# Sheet1.net
KiCad netlist of a schematic drawn in Altium Designer
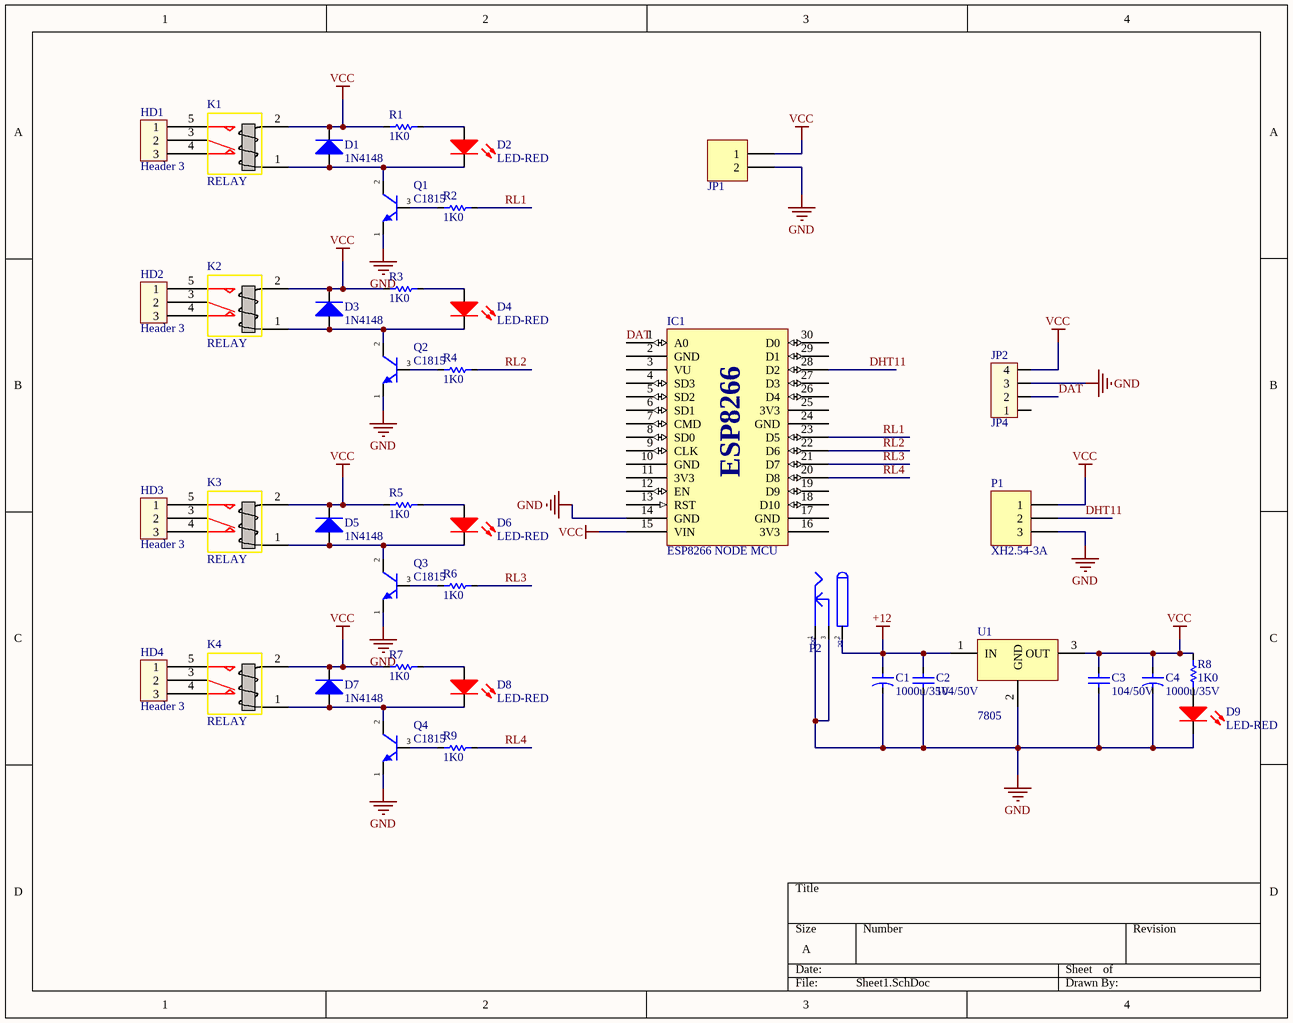
[diagram p0: Sheet1.SchDoc]

(export (version "E")
  (design (tool "Eeschema 10.0.6"))
  (components
    (comp (ref "C1")
      (value "1000u/35V")
      (footprint "CAP 13x25x5")
      (description "1000uF 35V Through Hole Aluminum Electrolytic Capacitor")
      (libsource (lib "Capacitors-Smile-Lib") (part "1000u/35V (13x25x5)"))
    )
    (comp (ref "C2")
      (value "104/50V")
      (footprint "CAP_NP_100")
      (libsource (lib "Capacitors-Smile-Lib") (part "CER-104-50V"))
    )
    (comp (ref "C3")
      (value "104/50V")
      (footprint "CAP_NP_100")
      (libsource (lib "Capacitors-Smile-Lib") (part "CER-104-50V"))
    )
    (comp (ref "C4")
      (value "1000u/35V")
      (footprint "CAP 13x25x5")
      (description "1000uF 35V Through Hole Aluminum Electrolytic Capacitor")
      (libsource (lib "Capacitors-Smile-Lib") (part "1000u/35V (13x25x5)"))
    )
    (comp (ref "D1")
      (value "1N4148")
      (footprint "DO35-GLASS-300MIL")
      (description "0.2A 75V Diode Standard Through Hole DO-35")
      (libsource (lib "Diodes-Smile-Lib") (part "1N4148 DO35"))
    )
    (comp (ref "D2")
      (value "LED-RED")
      (footprint "LED-3mm")
      (libsource (lib "LED-Smile-Lib") (part "LED-3MM-RED-LENS_RED"))
    )
    (comp (ref "D3")
      (value "1N4148")
      (footprint "DO35-GLASS-300MIL")
      (description "0.2A 75V Diode Standard Through Hole DO-35")
      (libsource (lib "Diodes-Smile-Lib") (part "1N4148 DO35"))
    )
    (comp (ref "D4")
      (value "LED-RED")
      (footprint "LED-3mm")
      (libsource (lib "LED-Smile-Lib") (part "LED-3MM-RED-LENS_RED"))
    )
    (comp (ref "D5")
      (value "1N4148")
      (footprint "DO35-GLASS-300MIL")
      (description "0.2A 75V Diode Standard Through Hole DO-35")
      (libsource (lib "Diodes-Smile-Lib") (part "1N4148 DO35"))
    )
    (comp (ref "D6")
      (value "LED-RED")
      (footprint "LED-3mm")
      (libsource (lib "LED-Smile-Lib") (part "LED-3MM-RED-LENS_RED"))
    )
    (comp (ref "D7")
      (value "1N4148")
      (footprint "DO35-GLASS-300MIL")
      (description "0.2A 75V Diode Standard Through Hole DO-35")
      (libsource (lib "Diodes-Smile-Lib") (part "1N4148 DO35"))
    )
    (comp (ref "D8")
      (value "LED-RED")
      (footprint "LED-3mm")
      (libsource (lib "LED-Smile-Lib") (part "LED-3MM-RED-LENS_RED"))
    )
    (comp (ref "D9")
      (value "LED-RED")
      (footprint "LED-3mm")
      (libsource (lib "LED-Smile-Lib") (part "LED-3MM-RED-LENS_RED"))
    )
    (comp (ref "HD1")
      (value "Header 3")
      (footprint "HED3")
      (description "Header 3 (Green)")
      (libsource (lib "syhaunguyen") (part "Hed3"))
    )
    (comp (ref "HD2")
      (value "Header 3")
      (footprint "HED3")
      (description "Header 3 (Green)")
      (libsource (lib "syhaunguyen") (part "Hed3"))
    )
    (comp (ref "HD3")
      (value "Header 3")
      (footprint "HED3")
      (description "Header 3 (Green)")
      (libsource (lib "syhaunguyen") (part "Hed3"))
    )
    (comp (ref "HD4")
      (value "Header 3")
      (footprint "HED3")
      (description "Header 3 (Green)")
      (libsource (lib "syhaunguyen") (part "Hed3"))
    )
    (comp (ref "IC1")
      (value "ESP8266 NODE MCU")
      (footprint "ESP8266 NodeMCU")
      (description "LUA-ESP8266 Wifi Module Techmt.vn")
      (libsource (lib "thuviencuatu") (part "ESP8266 NodeMCU"))
    )
    (comp (ref "JP1")
      (value "Header 2_1")
      (footprint "HED2")
      (description "Header, 2-Pin")
      (fields (field (name "MANUFACTURER") "Generic Components"))
      (libsource (lib "syhaunguyen") (part "Header 2_1"))
    )
    (comp (ref "JP2")
      (value "JP4")
      (footprint "CON4")
      (description "Connector 4")
      (libsource (lib "syhaunguyen") (part "Con4"))
    )
    (comp (ref "K1")
      (value "RELAY")
      (footprint "RELAY 12V_112D1")
      (libsource (lib "Relay-Smile-Lib") (part "RELAY 4"))
    )
    (comp (ref "K2")
      (value "RELAY")
      (footprint "RELAY 12V_112D1")
      (libsource (lib "Relay-Smile-Lib") (part "RELAY 4"))
    )
    (comp (ref "K3")
      (value "RELAY")
      (footprint "RELAY 12V_112D1")
      (libsource (lib "Relay-Smile-Lib") (part "RELAY 4"))
    )
    (comp (ref "K4")
      (value "RELAY")
      (footprint "RELAY 12V_112D1")
      (libsource (lib "Relay-Smile-Lib") (part "RELAY 4"))
    )
    (comp (ref "P1")
      (value "XH2.54-3A")
      (footprint "XH2.54-3A")
      (libsource (lib "XH2.54-Smile-Lib") (part "XH2.54-3A"))
    )
    (comp (ref "P2")
      (value "DC005")
      (footprint "JACK DC 5.5x2")
      (description "Jack DC 5.5x2.1")
      (libsource (lib "Power Jack-Smile-Lib") (part "JACK DC5.5x2.1"))
    )
    (comp (ref "Q1")
      (value "C1815")
      (footprint "TO-92")
      (description "TRANS NPN 50V 0.15A TO-92")
      (libsource (lib "BJT-Smile-Lib") (part "C1815-TO92"))
    )
    (comp (ref "Q2")
      (value "C1815")
      (footprint "TO-92")
      (description "TRANS NPN 50V 0.15A TO-92")
      (libsource (lib "BJT-Smile-Lib") (part "C1815-TO92"))
    )
    (comp (ref "Q3")
      (value "C1815")
      (footprint "TO-92")
      (description "TRANS NPN 50V 0.15A TO-92")
      (libsource (lib "BJT-Smile-Lib") (part "C1815-TO92"))
    )
    (comp (ref "Q4")
      (value "C1815")
      (footprint "TO-92")
      (description "TRANS NPN 50V 0.15A TO-92")
      (libsource (lib "BJT-Smile-Lib") (part "C1815-TO92"))
    )
    (comp (ref "R1")
      (value "1K0")
      (footprint "R-300mil")
      (description "RES 1K OHM 1/4W 5% CARBON FILM")
      (libsource (lib "RES-0.25W-Smile-Lib") (part "R-1/4W-5%-1K0"))
    )
    (comp (ref "R2")
      (value "1K0")
      (footprint "R-300mil")
      (description "RES 1K OHM 1/4W 5% CARBON FILM")
      (libsource (lib "RES-0.25W-Smile-Lib") (part "R-1/4W-5%-1K0"))
    )
    (comp (ref "R3")
      (value "1K0")
      (footprint "R-300mil")
      (description "RES 1K OHM 1/4W 5% CARBON FILM")
      (libsource (lib "RES-0.25W-Smile-Lib") (part "R-1/4W-5%-1K0"))
    )
    (comp (ref "R4")
      (value "1K0")
      (footprint "R-300mil")
      (description "RES 1K OHM 1/4W 5% CARBON FILM")
      (libsource (lib "RES-0.25W-Smile-Lib") (part "R-1/4W-5%-1K0"))
    )
    (comp (ref "R5")
      (value "1K0")
      (footprint "R-300mil")
      (description "RES 1K OHM 1/4W 5% CARBON FILM")
      (libsource (lib "RES-0.25W-Smile-Lib") (part "R-1/4W-5%-1K0"))
    )
    (comp (ref "R6")
      (value "1K0")
      (footprint "R-300mil")
      (description "RES 1K OHM 1/4W 5% CARBON FILM")
      (libsource (lib "RES-0.25W-Smile-Lib") (part "R-1/4W-5%-1K0"))
    )
    (comp (ref "R7")
      (value "1K0")
      (footprint "R-300mil")
      (description "RES 1K OHM 1/4W 5% CARBON FILM")
      (libsource (lib "RES-0.25W-Smile-Lib") (part "R-1/4W-5%-1K0"))
    )
    (comp (ref "R8")
      (value "1K0")
      (footprint "R-300mil")
      (description "RES 1K OHM 1/4W 5% CARBON FILM")
      (libsource (lib "RES-0.25W-Smile-Lib") (part "R-1/4W-5%-1K0"))
    )
    (comp (ref "R9")
      (value "1K0")
      (footprint "R-300mil")
      (description "RES 1K OHM 1/4W 5% CARBON FILM")
      (libsource (lib "RES-0.25W-Smile-Lib") (part "R-1/4W-5%-1K0"))
    )
    (comp (ref "U1")
      (value "7805")
      (footprint "TO 220+TN")
      (description "Linear Voltage Regulator IC Positive Fixed 1 Output 5V 1A TO-220AB")
      (libsource (lib "Linear Regulator-Smile-Lib") (part "7805 TO-220"))
    )
  )
  (nets
    (net (code "1") (name "+12") (class "Default")
      (node (ref "C1") (pin "1") (pinfunction "1_1") (pintype "passive"))
      (node (ref "C2") (pin "1") (pinfunction "1_1") (pintype "passive"))
      (node (ref "P2") (pin "2") (pinfunction "2_2") (pintype "power_in"))
      (node (ref "U1") (pin "1") (pinfunction "IN_1") (pintype "power_in"))
    )
    (net (code "2") (name "/DAT") (class "Default")
      (node (ref "IC1") (pin "1") (pinfunction "A0_1") (pintype "bidirectional"))
      (node (ref "JP2") (pin "2") (pinfunction "2_2") (pintype "passive"))
    )
    (net (code "3") (name "/DHT11") (class "Default")
      (node (ref "IC1") (pin "28") (pinfunction "D2_28") (pintype "bidirectional"))
      (node (ref "P1") (pin "2") (pinfunction "2_2") (pintype "passive"))
    )
    (net (code "4") (name "/RL1") (class "Default")
      (node (ref "IC1") (pin "23") (pinfunction "D5_23") (pintype "bidirectional"))
      (node (ref "R2") (pin "1") (pinfunction "1_1") (pintype "passive"))
    )
    (net (code "5") (name "/RL2") (class "Default")
      (node (ref "IC1") (pin "22") (pinfunction "D6_22") (pintype "bidirectional"))
      (node (ref "R4") (pin "1") (pinfunction "1_1") (pintype "passive"))
    )
    (net (code "6") (name "/RL3") (class "Default")
      (node (ref "IC1") (pin "21") (pinfunction "D7_21") (pintype "bidirectional"))
      (node (ref "R6") (pin "1") (pinfunction "1_1") (pintype "passive"))
    )
    (net (code "7") (name "/RL4") (class "Default")
      (node (ref "IC1") (pin "20") (pinfunction "D8_20") (pintype "bidirectional"))
      (node (ref "R9") (pin "1") (pinfunction "1_1") (pintype "passive"))
    )
    (net (code "8") (name "GND") (class "Default")
      (node (ref "C1") (pin "2") (pinfunction "2_2") (pintype "passive"))
      (node (ref "C2") (pin "2") (pinfunction "2_2") (pintype "passive"))
      (node (ref "C3") (pin "2") (pinfunction "2_2") (pintype "passive"))
      (node (ref "C4") (pin "2") (pinfunction "2_2") (pintype "passive"))
      (node (ref "D9") (pin "2") (pinfunction "K_2") (pintype "passive"))
      (node (ref "IC1") (pin "14") (pinfunction "GND_14") (pintype "power_in"))
      (node (ref "JP1") (pin "2") (pinfunction "2_2") (pintype "passive"))
      (node (ref "JP2") (pin "3") (pinfunction "3_3") (pintype "passive"))
      (node (ref "P1") (pin "3") (pinfunction "3_3") (pintype "passive"))
      (node (ref "P2") (pin "1") (pinfunction "1_1") (pintype "power_in"))
      (node (ref "P2") (pin "3") (pinfunction "3_3") (pintype "power_in"))
      (node (ref "Q1") (pin "1") (pinfunction "E_1") (pintype "passive"))
      (node (ref "Q2") (pin "1") (pinfunction "E_1") (pintype "passive"))
      (node (ref "Q3") (pin "1") (pinfunction "E_1") (pintype "passive"))
      (node (ref "Q4") (pin "1") (pinfunction "E_1") (pintype "passive"))
      (node (ref "U1") (pin "2") (pinfunction "GND_2") (pintype "power_in"))
    )
    (net (code "9") (name "Net-(D1-A)") (class "Default")
      (node (ref "D1") (pin "1") (pinfunction "A_1") (pintype "passive"))
      (node (ref "D2") (pin "2") (pinfunction "K_2") (pintype "passive"))
      (node (ref "K1") (pin "1") (pinfunction "Coil1_1") (pintype "passive"))
      (node (ref "Q1") (pin "2") (pinfunction "C_2") (pintype "passive"))
    )
    (net (code "10") (name "Net-(D2-A)") (class "Default")
      (node (ref "D2") (pin "1") (pinfunction "A_1") (pintype "passive"))
      (node (ref "R1") (pin "1") (pinfunction "1_1") (pintype "passive"))
    )
    (net (code "11") (name "Net-(D3-A)") (class "Default")
      (node (ref "D3") (pin "1") (pinfunction "A_1") (pintype "passive"))
      (node (ref "D4") (pin "2") (pinfunction "K_2") (pintype "passive"))
      (node (ref "K2") (pin "1") (pinfunction "Coil1_1") (pintype "passive"))
      (node (ref "Q2") (pin "2") (pinfunction "C_2") (pintype "passive"))
    )
    (net (code "12") (name "Net-(D4-A)") (class "Default")
      (node (ref "D4") (pin "1") (pinfunction "A_1") (pintype "passive"))
      (node (ref "R3") (pin "1") (pinfunction "1_1") (pintype "passive"))
    )
    (net (code "13") (name "Net-(D5-A)") (class "Default")
      (node (ref "D5") (pin "1") (pinfunction "A_1") (pintype "passive"))
      (node (ref "D6") (pin "2") (pinfunction "K_2") (pintype "passive"))
      (node (ref "K3") (pin "1") (pinfunction "Coil1_1") (pintype "passive"))
      (node (ref "Q3") (pin "2") (pinfunction "C_2") (pintype "passive"))
    )
    (net (code "14") (name "Net-(D6-A)") (class "Default")
      (node (ref "D6") (pin "1") (pinfunction "A_1") (pintype "passive"))
      (node (ref "R5") (pin "1") (pinfunction "1_1") (pintype "passive"))
    )
    (net (code "15") (name "Net-(D7-A)") (class "Default")
      (node (ref "D7") (pin "1") (pinfunction "A_1") (pintype "passive"))
      (node (ref "D8") (pin "2") (pinfunction "K_2") (pintype "passive"))
      (node (ref "K4") (pin "1") (pinfunction "Coil1_1") (pintype "passive"))
      (node (ref "Q4") (pin "2") (pinfunction "C_2") (pintype "passive"))
    )
    (net (code "16") (name "Net-(D8-A)") (class "Default")
      (node (ref "D8") (pin "1") (pinfunction "A_1") (pintype "passive"))
      (node (ref "R7") (pin "1") (pinfunction "1_1") (pintype "passive"))
    )
    (net (code "17") (name "Net-(D9-A)") (class "Default")
      (node (ref "D9") (pin "1") (pinfunction "A_1") (pintype "passive"))
      (node (ref "R8") (pin "2") (pinfunction "2_2") (pintype "passive"))
    )
    (net (code "18") (name "Net-(K1-COM)") (class "Default")
      (node (ref "HD1") (pin "2") (pinfunction "2_2") (pintype "passive"))
      (node (ref "K1") (pin "3") (pinfunction "COM_3") (pintype "passive"))
    )
    (net (code "19") (name "Net-(K1-NC)") (class "Default")
      (node (ref "HD1") (pin "1") (pinfunction "1_1") (pintype "passive"))
      (node (ref "K1") (pin "5") (pinfunction "NC_5") (pintype "passive"))
    )
    (net (code "20") (name "Net-(K1-NO)") (class "Default")
      (node (ref "HD1") (pin "3") (pinfunction "3_3") (pintype "passive"))
      (node (ref "K1") (pin "4") (pinfunction "NO_4") (pintype "passive"))
    )
    (net (code "21") (name "Net-(K2-COM)") (class "Default")
      (node (ref "HD2") (pin "2") (pinfunction "2_2") (pintype "passive"))
      (node (ref "K2") (pin "3") (pinfunction "COM_3") (pintype "passive"))
    )
    (net (code "22") (name "Net-(K2-NC)") (class "Default")
      (node (ref "HD2") (pin "1") (pinfunction "1_1") (pintype "passive"))
      (node (ref "K2") (pin "5") (pinfunction "NC_5") (pintype "passive"))
    )
    (net (code "23") (name "Net-(K2-NO)") (class "Default")
      (node (ref "HD2") (pin "3") (pinfunction "3_3") (pintype "passive"))
      (node (ref "K2") (pin "4") (pinfunction "NO_4") (pintype "passive"))
    )
    (net (code "24") (name "Net-(K3-COM)") (class "Default")
      (node (ref "HD3") (pin "2") (pinfunction "2_2") (pintype "passive"))
      (node (ref "K3") (pin "3") (pinfunction "COM_3") (pintype "passive"))
    )
    (net (code "25") (name "Net-(K3-NC)") (class "Default")
      (node (ref "HD3") (pin "1") (pinfunction "1_1") (pintype "passive"))
      (node (ref "K3") (pin "5") (pinfunction "NC_5") (pintype "passive"))
    )
    (net (code "26") (name "Net-(K3-NO)") (class "Default")
      (node (ref "HD3") (pin "3") (pinfunction "3_3") (pintype "passive"))
      (node (ref "K3") (pin "4") (pinfunction "NO_4") (pintype "passive"))
    )
    (net (code "27") (name "Net-(K4-COM)") (class "Default")
      (node (ref "HD4") (pin "2") (pinfunction "2_2") (pintype "passive"))
      (node (ref "K4") (pin "3") (pinfunction "COM_3") (pintype "passive"))
    )
    (net (code "28") (name "Net-(K4-NC)") (class "Default")
      (node (ref "HD4") (pin "1") (pinfunction "1_1") (pintype "passive"))
      (node (ref "K4") (pin "5") (pinfunction "NC_5") (pintype "passive"))
    )
    (net (code "29") (name "Net-(K4-NO)") (class "Default")
      (node (ref "HD4") (pin "3") (pinfunction "3_3") (pintype "passive"))
      (node (ref "K4") (pin "4") (pinfunction "NO_4") (pintype "passive"))
    )
    (net (code "30") (name "Net-(Q1-B)") (class "Default")
      (node (ref "Q1") (pin "3") (pinfunction "B_3") (pintype "passive"))
      (node (ref "R2") (pin "2") (pinfunction "2_2") (pintype "passive"))
    )
    (net (code "31") (name "Net-(Q2-B)") (class "Default")
      (node (ref "Q2") (pin "3") (pinfunction "B_3") (pintype "passive"))
      (node (ref "R4") (pin "2") (pinfunction "2_2") (pintype "passive"))
    )
    (net (code "32") (name "Net-(Q3-B)") (class "Default")
      (node (ref "Q3") (pin "3") (pinfunction "B_3") (pintype "passive"))
      (node (ref "R6") (pin "2") (pinfunction "2_2") (pintype "passive"))
    )
    (net (code "33") (name "Net-(Q4-B)") (class "Default")
      (node (ref "Q4") (pin "3") (pinfunction "B_3") (pintype "passive"))
      (node (ref "R9") (pin "2") (pinfunction "2_2") (pintype "passive"))
    )
    (net (code "34") (name "VCC") (class "Default")
      (node (ref "C3") (pin "1") (pinfunction "1_1") (pintype "passive"))
      (node (ref "C4") (pin "1") (pinfunction "1_1") (pintype "passive"))
      (node (ref "D1") (pin "2") (pinfunction "K_2") (pintype "passive"))
      (node (ref "D3") (pin "2") (pinfunction "K_2") (pintype "passive"))
      (node (ref "D5") (pin "2") (pinfunction "K_2") (pintype "passive"))
      (node (ref "D7") (pin "2") (pinfunction "K_2") (pintype "passive"))
      (node (ref "IC1") (pin "15") (pinfunction "VIN_15") (pintype "power_in"))
      (node (ref "JP1") (pin "1") (pinfunction "1_1") (pintype "passive"))
      (node (ref "JP2") (pin "4") (pinfunction "4_4") (pintype "passive"))
      (node (ref "K1") (pin "2") (pinfunction "Coil2_2") (pintype "passive"))
      (node (ref "K2") (pin "2") (pinfunction "Coil2_2") (pintype "passive"))
      (node (ref "K3") (pin "2") (pinfunction "Coil2_2") (pintype "passive"))
      (node (ref "K4") (pin "2") (pinfunction "Coil2_2") (pintype "passive"))
      (node (ref "P1") (pin "1") (pinfunction "1_1") (pintype "passive"))
      (node (ref "R1") (pin "2") (pinfunction "2_2") (pintype "passive"))
      (node (ref "R3") (pin "2") (pinfunction "2_2") (pintype "passive"))
      (node (ref "R5") (pin "2") (pinfunction "2_2") (pintype "passive"))
      (node (ref "R7") (pin "2") (pinfunction "2_2") (pintype "passive"))
      (node (ref "R8") (pin "1") (pinfunction "1_1") (pintype "passive"))
      (node (ref "U1") (pin "3") (pinfunction "OUT_3") (pintype "power_in"))
    )
    (net (code "35") (name "unconnected-(IC1-3V3-Pad11)") (class "Default")
      (node (ref "IC1") (pin "11") (pinfunction "3V3_11") (pintype "power_in"))
    )
    (net (code "36") (name "unconnected-(IC1-3V3-Pad16)") (class "Default")
      (node (ref "IC1") (pin "16") (pinfunction "3V3_16") (pintype "power_in"))
    )
    (net (code "37") (name "unconnected-(IC1-3V3-Pad25)") (class "Default")
      (node (ref "IC1") (pin "25") (pinfunction "3V3_25") (pintype "power_in"))
    )
    (net (code "38") (name "unconnected-(IC1-CLK-Pad9)") (class "Default")
      (node (ref "IC1") (pin "9") (pinfunction "CLK_9") (pintype "bidirectional"))
    )
    (net (code "39") (name "unconnected-(IC1-CMD-Pad7)") (class "Default")
      (node (ref "IC1") (pin "7") (pinfunction "CMD_7") (pintype "bidirectional"))
    )
    (net (code "40") (name "unconnected-(IC1-D0-Pad30)") (class "Default")
      (node (ref "IC1") (pin "30") (pinfunction "D0_30") (pintype "bidirectional"))
    )
    (net (code "41") (name "unconnected-(IC1-D1-Pad29)") (class "Default")
      (node (ref "IC1") (pin "29") (pinfunction "D1_29") (pintype "bidirectional"))
    )
    (net (code "42") (name "unconnected-(IC1-D3-Pad27)") (class "Default")
      (node (ref "IC1") (pin "27") (pinfunction "D3_27") (pintype "bidirectional"))
    )
    (net (code "43") (name "unconnected-(IC1-D4-Pad26)") (class "Default")
      (node (ref "IC1") (pin "26") (pinfunction "D4_26") (pintype "bidirectional"))
    )
    (net (code "44") (name "unconnected-(IC1-D9-Pad19)") (class "Default")
      (node (ref "IC1") (pin "19") (pinfunction "D9_19") (pintype "bidirectional"))
    )
    (net (code "45") (name "unconnected-(IC1-D10-Pad18)") (class "Default")
      (node (ref "IC1") (pin "18") (pinfunction "D10_18") (pintype "bidirectional"))
    )
    (net (code "46") (name "unconnected-(IC1-EN-Pad12)") (class "Default")
      (node (ref "IC1") (pin "12") (pinfunction "EN_12") (pintype "bidirectional"))
    )
    (net (code "47") (name "unconnected-(IC1-GND-Pad2)") (class "Default")
      (node (ref "IC1") (pin "2") (pinfunction "GND_2") (pintype "power_in"))
    )
    (net (code "48") (name "unconnected-(IC1-GND-Pad10)") (class "Default")
      (node (ref "IC1") (pin "10") (pinfunction "GND_10") (pintype "power_in"))
    )
    (net (code "49") (name "unconnected-(IC1-GND-Pad17)") (class "Default")
      (node (ref "IC1") (pin "17") (pinfunction "GND_17") (pintype "power_in"))
    )
    (net (code "50") (name "unconnected-(IC1-GND-Pad24)") (class "Default")
      (node (ref "IC1") (pin "24") (pinfunction "GND_24") (pintype "power_in"))
    )
    (net (code "51") (name "unconnected-(IC1-RST-Pad13)") (class "Default")
      (node (ref "IC1") (pin "13") (pinfunction "RST_13") (pintype "input"))
    )
    (net (code "52") (name "unconnected-(IC1-SD0-Pad8)") (class "Default")
      (node (ref "IC1") (pin "8") (pinfunction "SD0_8") (pintype "bidirectional"))
    )
    (net (code "53") (name "unconnected-(IC1-SD1-Pad6)") (class "Default")
      (node (ref "IC1") (pin "6") (pinfunction "SD1_6") (pintype "bidirectional"))
    )
    (net (code "54") (name "unconnected-(IC1-SD2-Pad5)") (class "Default")
      (node (ref "IC1") (pin "5") (pinfunction "SD2_5") (pintype "bidirectional"))
    )
    (net (code "55") (name "unconnected-(IC1-SD3-Pad4)") (class "Default")
      (node (ref "IC1") (pin "4") (pinfunction "SD3_4") (pintype "bidirectional"))
    )
    (net (code "56") (name "unconnected-(IC1-VU-Pad3)") (class "Default")
      (node (ref "IC1") (pin "3") (pinfunction "VU_3") (pintype "power_in"))
    )
    (net (code "57") (name "unconnected-(JP2-Pad1)") (class "Default")
      (node (ref "JP2") (pin "1") (pinfunction "1_1") (pintype "passive"))
    )
  )
)
